# Main_bord.net
KiCad netlist of a schematic drawn in EAGLE
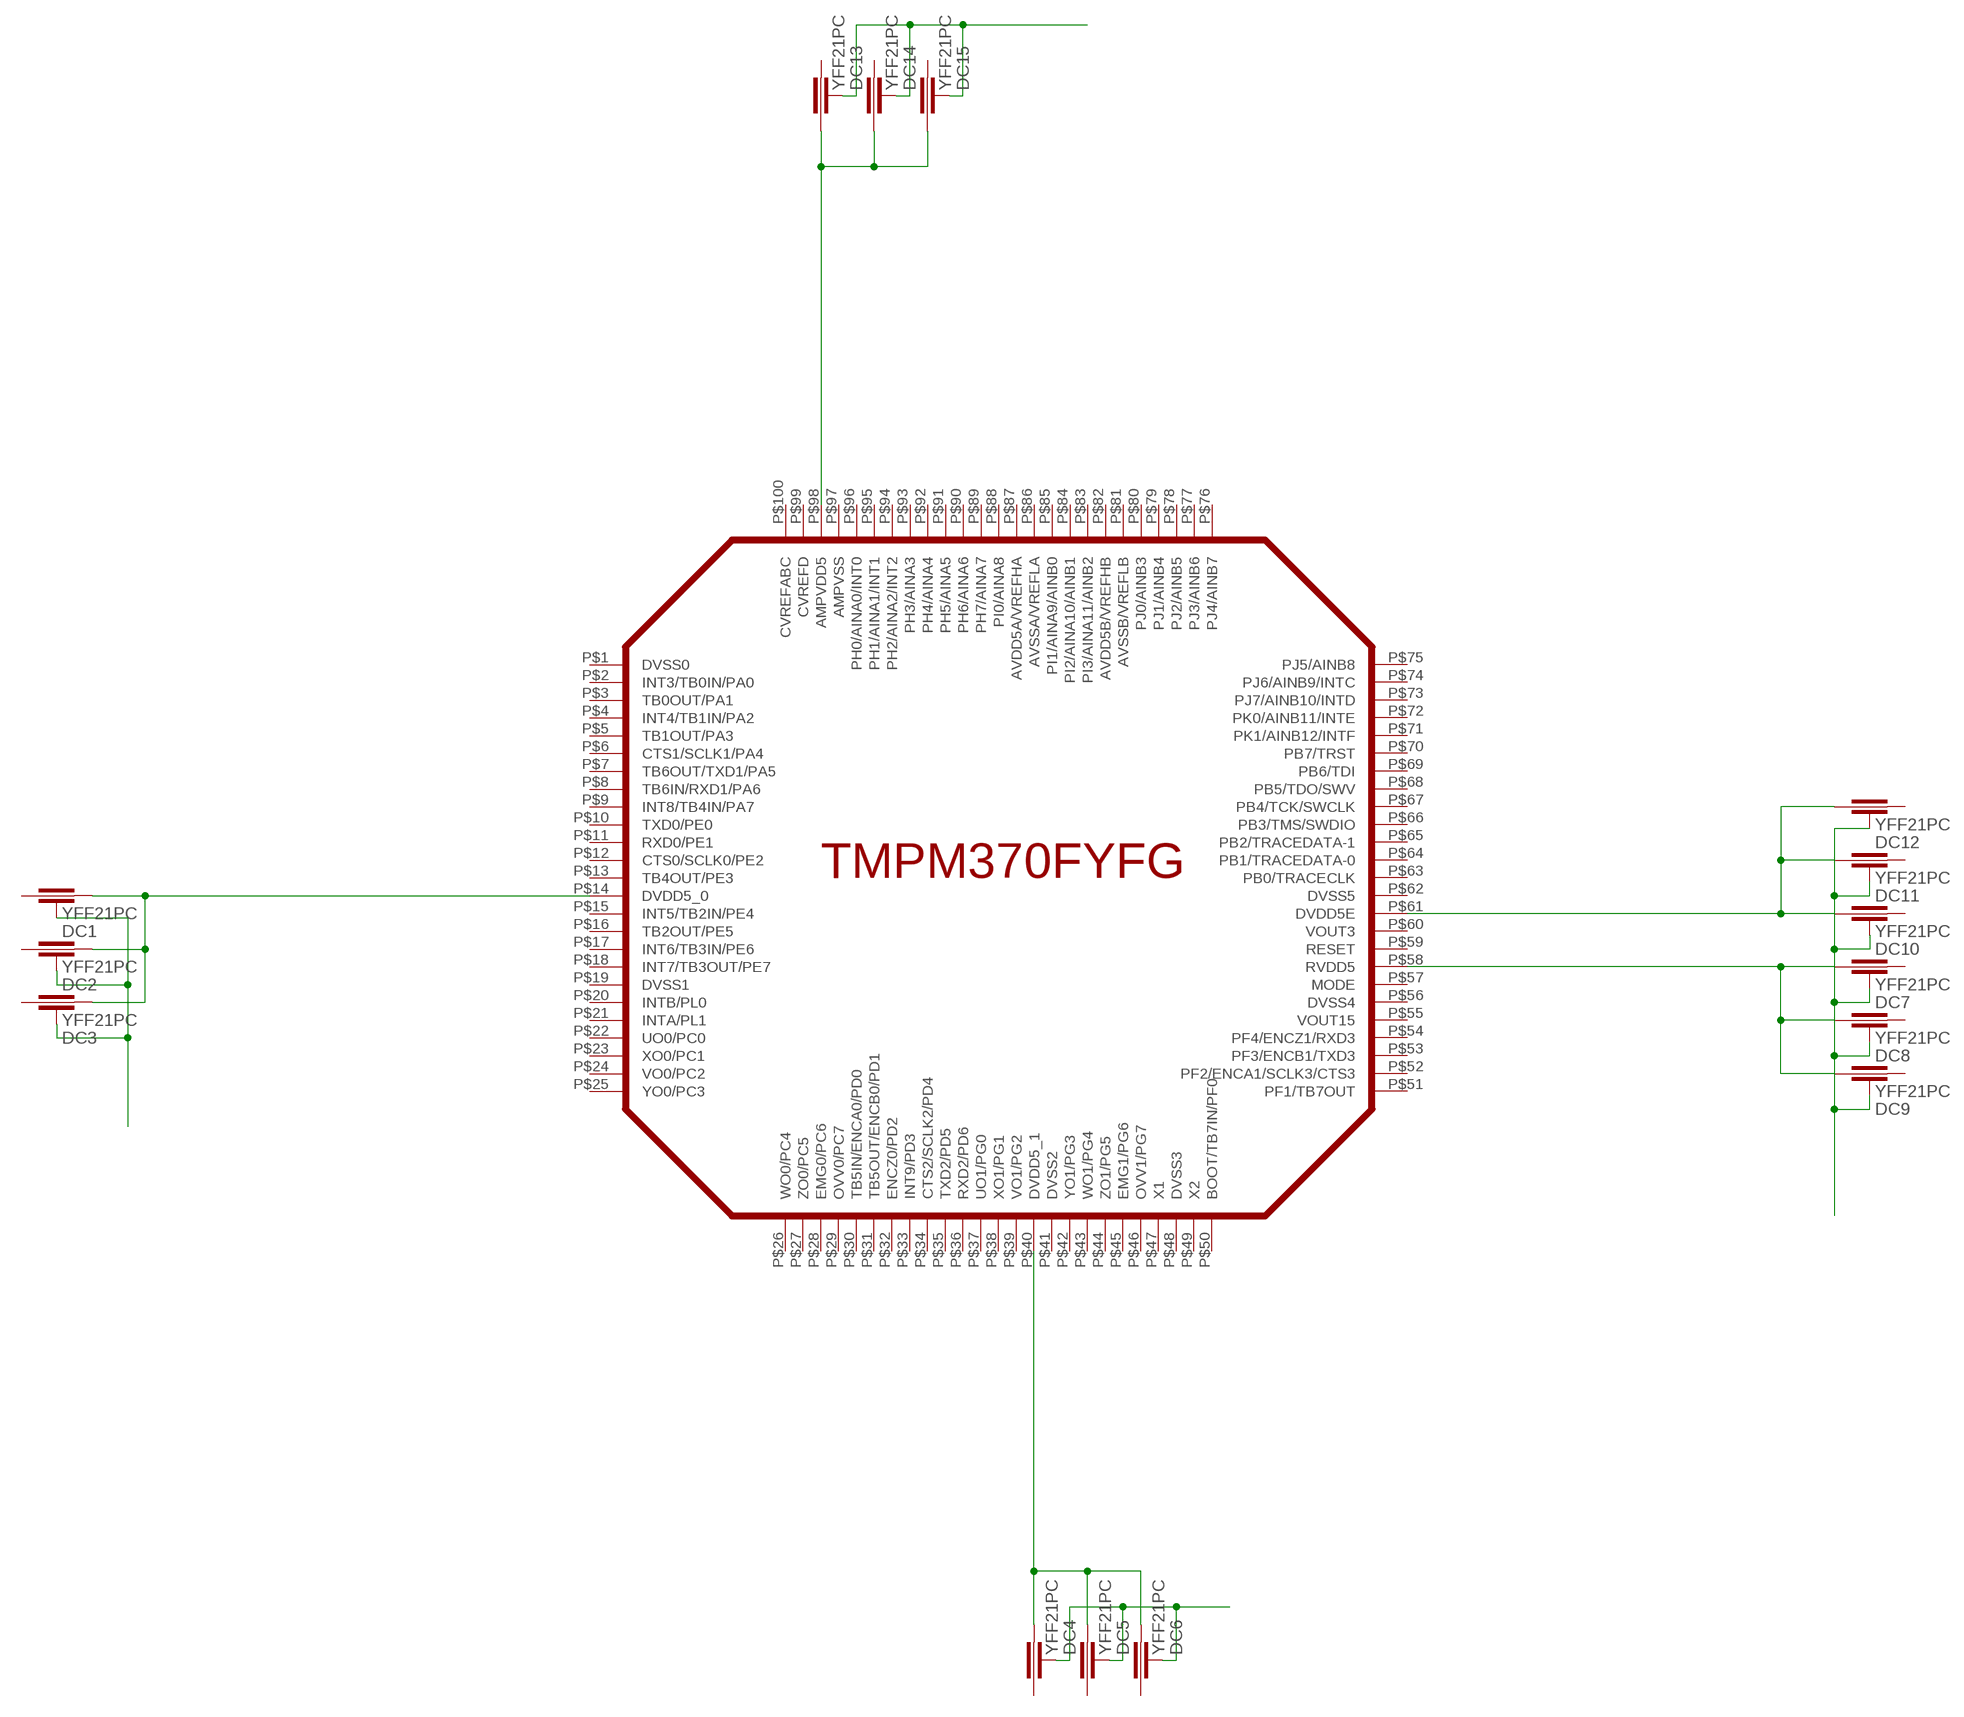
[diagram p0: schematic, sheet 1]

(export (version "E")
  (design (tool "Eeschema 10.0.6"))
  (components
    (comp (ref "DC1")
      (value "YFF21PC")
      (footprint "eagle-import:YFF21PC")
      (libsource (lib "eagle-import") (part "YFF21PC"))
    )
    (comp (ref "DC2")
      (value "YFF21PC")
      (footprint "eagle-import:YFF21PC")
      (libsource (lib "eagle-import") (part "YFF21PC"))
    )
    (comp (ref "DC3")
      (value "YFF21PC")
      (footprint "eagle-import:YFF21PC")
      (libsource (lib "eagle-import") (part "YFF21PC"))
    )
    (comp (ref "DC4")
      (value "YFF21PC")
      (footprint "eagle-import:YFF21PC")
      (libsource (lib "eagle-import") (part "YFF21PC"))
    )
    (comp (ref "DC5")
      (value "YFF21PC")
      (footprint "eagle-import:YFF21PC")
      (libsource (lib "eagle-import") (part "YFF21PC"))
    )
    (comp (ref "DC6")
      (value "YFF21PC")
      (footprint "eagle-import:YFF21PC")
      (libsource (lib "eagle-import") (part "YFF21PC"))
    )
    (comp (ref "DC7")
      (value "YFF21PC")
      (footprint "eagle-import:YFF21PC")
      (libsource (lib "eagle-import") (part "YFF21PC"))
    )
    (comp (ref "DC8")
      (value "YFF21PC")
      (footprint "eagle-import:YFF21PC")
      (libsource (lib "eagle-import") (part "YFF21PC"))
    )
    (comp (ref "DC9")
      (value "YFF21PC")
      (footprint "eagle-import:YFF21PC")
      (libsource (lib "eagle-import") (part "YFF21PC"))
    )
    (comp (ref "DC10")
      (value "YFF21PC")
      (footprint "eagle-import:YFF21PC")
      (libsource (lib "eagle-import") (part "YFF21PC"))
    )
    (comp (ref "DC11")
      (value "YFF21PC")
      (footprint "eagle-import:YFF21PC")
      (libsource (lib "eagle-import") (part "YFF21PC"))
    )
    (comp (ref "DC12")
      (value "YFF21PC")
      (footprint "eagle-import:YFF21PC")
      (libsource (lib "eagle-import") (part "YFF21PC"))
    )
    (comp (ref "DC13")
      (value "YFF21PC")
      (footprint "eagle-import:YFF21PC")
      (libsource (lib "eagle-import") (part "YFF21PC"))
    )
    (comp (ref "DC14")
      (value "YFF21PC")
      (footprint "eagle-import:YFF21PC")
      (libsource (lib "eagle-import") (part "YFF21PC"))
    )
    (comp (ref "DC15")
      (value "YFF21PC")
      (footprint "eagle-import:YFF21PC")
      (libsource (lib "eagle-import") (part "YFF21PC"))
    )
    (comp (ref "IC1")
      (value "TMPM370FYFG")
      (footprint "eagle-import:LQFP100-P-1414-0.50H")
      (libsource (lib "eagle-import") (part "TMPM370FYFG"))
    )
  )
  (nets
    (net (code "1") (name "Net-(DC1-GND-PadGND1)") (class "Default")
      (node (ref "DC1") (pin "GND1") (pinfunction "GND_GND1") (pintype "bidirectional"))
      (node (ref "DC1") (pin "GND2") (pinfunction "GND_GND2") (pintype "bidirectional"))
      (node (ref "DC2") (pin "GND1") (pinfunction "GND_GND1") (pintype "bidirectional"))
      (node (ref "DC2") (pin "GND2") (pinfunction "GND_GND2") (pintype "bidirectional"))
      (node (ref "DC3") (pin "GND1") (pinfunction "GND_GND1") (pintype "bidirectional"))
      (node (ref "DC3") (pin "GND2") (pinfunction "GND_GND2") (pintype "bidirectional"))
    )
    (net (code "2") (name "Net-(DC4-GND-PadGND1)") (class "Default")
      (node (ref "DC4") (pin "GND1") (pinfunction "GND_GND1") (pintype "bidirectional"))
      (node (ref "DC4") (pin "GND2") (pinfunction "GND_GND2") (pintype "bidirectional"))
      (node (ref "DC5") (pin "GND1") (pinfunction "GND_GND1") (pintype "bidirectional"))
      (node (ref "DC5") (pin "GND2") (pinfunction "GND_GND2") (pintype "bidirectional"))
      (node (ref "DC6") (pin "GND1") (pinfunction "GND_GND1") (pintype "bidirectional"))
      (node (ref "DC6") (pin "GND2") (pinfunction "GND_GND2") (pintype "bidirectional"))
    )
    (net (code "3") (name "Net-(DC10-GND-PadGND1)") (class "Default")
      (node (ref "DC10") (pin "GND1") (pinfunction "GND_GND1") (pintype "bidirectional"))
      (node (ref "DC10") (pin "GND2") (pinfunction "GND_GND2") (pintype "bidirectional"))
      (node (ref "DC11") (pin "GND1") (pinfunction "GND_GND1") (pintype "bidirectional"))
      (node (ref "DC11") (pin "GND2") (pinfunction "GND_GND2") (pintype "bidirectional"))
      (node (ref "DC12") (pin "GND1") (pinfunction "GND_GND1") (pintype "bidirectional"))
      (node (ref "DC12") (pin "GND2") (pinfunction "GND_GND2") (pintype "bidirectional"))
      (node (ref "DC7") (pin "GND1") (pinfunction "GND_GND1") (pintype "bidirectional"))
      (node (ref "DC7") (pin "GND2") (pinfunction "GND_GND2") (pintype "bidirectional"))
      (node (ref "DC8") (pin "GND1") (pinfunction "GND_GND1") (pintype "bidirectional"))
      (node (ref "DC8") (pin "GND2") (pinfunction "GND_GND2") (pintype "bidirectional"))
      (node (ref "DC9") (pin "GND1") (pinfunction "GND_GND1") (pintype "bidirectional"))
      (node (ref "DC9") (pin "GND2") (pinfunction "GND_GND2") (pintype "bidirectional"))
    )
    (net (code "4") (name "Net-(DC13-GND-PadGND1)") (class "Default")
      (node (ref "DC13") (pin "GND1") (pinfunction "GND_GND1") (pintype "bidirectional"))
      (node (ref "DC13") (pin "GND2") (pinfunction "GND_GND2") (pintype "bidirectional"))
      (node (ref "DC14") (pin "GND1") (pinfunction "GND_GND1") (pintype "bidirectional"))
      (node (ref "DC14") (pin "GND2") (pinfunction "GND_GND2") (pintype "bidirectional"))
      (node (ref "DC15") (pin "GND1") (pinfunction "GND_GND1") (pintype "bidirectional"))
      (node (ref "DC15") (pin "GND2") (pinfunction "GND_GND2") (pintype "bidirectional"))
    )
    (net (code "5") (name "Net-(IC1-AMPVDD5)") (class "Default")
      (node (ref "DC13") (pin "P$1") (pinfunction "P$1_P$1") (pintype "bidirectional"))
      (node (ref "DC14") (pin "P$1") (pinfunction "P$1_P$1") (pintype "bidirectional"))
      (node (ref "DC15") (pin "P$1") (pinfunction "P$1_P$1") (pintype "bidirectional"))
      (node (ref "IC1") (pin "P$98") (pinfunction "AMPVDD5_P$98") (pintype "bidirectional"))
    )
    (net (code "6") (name "Net-(IC1-DVDD5E)") (class "Default")
      (node (ref "DC10") (pin "P$1") (pinfunction "P$1_P$1") (pintype "bidirectional"))
      (node (ref "DC11") (pin "P$1") (pinfunction "P$1_P$1") (pintype "bidirectional"))
      (node (ref "DC12") (pin "P$1") (pinfunction "P$1_P$1") (pintype "bidirectional"))
      (node (ref "IC1") (pin "P$61") (pinfunction "DVDD5E_P$61") (pintype "bidirectional"))
    )
    (net (code "7") (name "Net-(IC1-DVDD5_0)") (class "Default")
      (node (ref "DC1") (pin "P$2") (pinfunction "P$2_P$2") (pintype "bidirectional"))
      (node (ref "DC2") (pin "P$2") (pinfunction "P$2_P$2") (pintype "bidirectional"))
      (node (ref "DC3") (pin "P$2") (pinfunction "P$2_P$2") (pintype "bidirectional"))
      (node (ref "IC1") (pin "P$14") (pinfunction "DVDD5_0_P$14") (pintype "bidirectional"))
    )
    (net (code "8") (name "Net-(IC1-DVDD5_1)") (class "Default")
      (node (ref "DC4") (pin "P$2") (pinfunction "P$2_P$2") (pintype "bidirectional"))
      (node (ref "DC5") (pin "P$2") (pinfunction "P$2_P$2") (pintype "bidirectional"))
      (node (ref "DC6") (pin "P$2") (pinfunction "P$2_P$2") (pintype "bidirectional"))
      (node (ref "IC1") (pin "P$40") (pinfunction "DVDD5_1_P$40") (pintype "bidirectional"))
    )
    (net (code "9") (name "Net-(IC1-RVDD5)") (class "Default")
      (node (ref "DC7") (pin "P$1") (pinfunction "P$1_P$1") (pintype "bidirectional"))
      (node (ref "DC8") (pin "P$1") (pinfunction "P$1_P$1") (pintype "bidirectional"))
      (node (ref "DC9") (pin "P$1") (pinfunction "P$1_P$1") (pintype "bidirectional"))
      (node (ref "IC1") (pin "P$58") (pinfunction "RVDD5_P$58") (pintype "bidirectional"))
    )
    (net (code "10") (name "unconnected-(DC1-PadP$1)") (class "Default")
      (node (ref "DC1") (pin "P$1") (pinfunction "P$1_P$1") (pintype "bidirectional"))
    )
    (net (code "11") (name "unconnected-(DC2-PadP$1)") (class "Default")
      (node (ref "DC2") (pin "P$1") (pinfunction "P$1_P$1") (pintype "bidirectional"))
    )
    (net (code "12") (name "unconnected-(DC3-PadP$1)") (class "Default")
      (node (ref "DC3") (pin "P$1") (pinfunction "P$1_P$1") (pintype "bidirectional"))
    )
    (net (code "13") (name "unconnected-(DC4-PadP$1)") (class "Default")
      (node (ref "DC4") (pin "P$1") (pinfunction "P$1_P$1") (pintype "bidirectional"))
    )
    (net (code "14") (name "unconnected-(DC5-PadP$1)") (class "Default")
      (node (ref "DC5") (pin "P$1") (pinfunction "P$1_P$1") (pintype "bidirectional"))
    )
    (net (code "15") (name "unconnected-(DC6-PadP$1)") (class "Default")
      (node (ref "DC6") (pin "P$1") (pinfunction "P$1_P$1") (pintype "bidirectional"))
    )
    (net (code "16") (name "unconnected-(DC7-PadP$2)") (class "Default")
      (node (ref "DC7") (pin "P$2") (pinfunction "P$2_P$2") (pintype "bidirectional"))
    )
    (net (code "17") (name "unconnected-(DC8-PadP$2)") (class "Default")
      (node (ref "DC8") (pin "P$2") (pinfunction "P$2_P$2") (pintype "bidirectional"))
    )
    (net (code "18") (name "unconnected-(DC9-PadP$2)") (class "Default")
      (node (ref "DC9") (pin "P$2") (pinfunction "P$2_P$2") (pintype "bidirectional"))
    )
    (net (code "19") (name "unconnected-(DC10-PadP$2)") (class "Default")
      (node (ref "DC10") (pin "P$2") (pinfunction "P$2_P$2") (pintype "bidirectional"))
    )
    (net (code "20") (name "unconnected-(DC11-PadP$2)") (class "Default")
      (node (ref "DC11") (pin "P$2") (pinfunction "P$2_P$2") (pintype "bidirectional"))
    )
    (net (code "21") (name "unconnected-(DC12-PadP$2)") (class "Default")
      (node (ref "DC12") (pin "P$2") (pinfunction "P$2_P$2") (pintype "bidirectional"))
    )
    (net (code "22") (name "unconnected-(DC13-PadP$2)") (class "Default")
      (node (ref "DC13") (pin "P$2") (pinfunction "P$2_P$2") (pintype "bidirectional"))
    )
    (net (code "23") (name "unconnected-(DC14-PadP$2)") (class "Default")
      (node (ref "DC14") (pin "P$2") (pinfunction "P$2_P$2") (pintype "bidirectional"))
    )
    (net (code "24") (name "unconnected-(DC15-PadP$2)") (class "Default")
      (node (ref "DC15") (pin "P$2") (pinfunction "P$2_P$2") (pintype "bidirectional"))
    )
    (net (code "25") (name "unconnected-(IC1-AMPVSS-PadP$97)") (class "Default")
      (node (ref "IC1") (pin "P$97") (pinfunction "AMPVSS_P$97") (pintype "bidirectional"))
    )
    (net (code "26") (name "unconnected-(IC1-AVDD5A{slash}VREFHA-PadP$87)") (class "Default")
      (node (ref "IC1") (pin "P$87") (pinfunction "AVDD5A/VREFHA_P$87") (pintype "bidirectional"))
    )
    (net (code "27") (name "unconnected-(IC1-AVDD5B{slash}VREFHB-PadP$82)") (class "Default")
      (node (ref "IC1") (pin "P$82") (pinfunction "AVDD5B/VREFHB_P$82") (pintype "bidirectional"))
    )
    (net (code "28") (name "unconnected-(IC1-AVSSA{slash}VREFLA-PadP$86)") (class "Default")
      (node (ref "IC1") (pin "P$86") (pinfunction "AVSSA/VREFLA_P$86") (pintype "bidirectional"))
    )
    (net (code "29") (name "unconnected-(IC1-AVSSB{slash}VREFLB-PadP$81)") (class "Default")
      (node (ref "IC1") (pin "P$81") (pinfunction "AVSSB/VREFLB_P$81") (pintype "bidirectional"))
    )
    (net (code "30") (name "unconnected-(IC1-BOOT{slash}TB7IN{slash}PF0-PadP$50)") (class "Default")
      (node (ref "IC1") (pin "P$50") (pinfunction "BOOT/TB7IN/PF0_P$50") (pintype "bidirectional"))
    )
    (net (code "31") (name "unconnected-(IC1-CTS0{slash}SCLK0{slash}PE2-PadP$12)") (class "Default")
      (node (ref "IC1") (pin "P$12") (pinfunction "CTS0/SCLK0/PE2_P$12") (pintype "bidirectional"))
    )
    (net (code "32") (name "unconnected-(IC1-CTS1{slash}SCLK1{slash}PA4-PadP$6)") (class "Default")
      (node (ref "IC1") (pin "P$6") (pinfunction "CTS1/SCLK1/PA4_P$6") (pintype "bidirectional"))
    )
    (net (code "33") (name "unconnected-(IC1-CTS2{slash}SCLK2{slash}PD4-PadP$34)") (class "Default")
      (node (ref "IC1") (pin "P$34") (pinfunction "CTS2/SCLK2/PD4_P$34") (pintype "bidirectional"))
    )
    (net (code "34") (name "unconnected-(IC1-CVREFABC-PadP$100)") (class "Default")
      (node (ref "IC1") (pin "P$100") (pinfunction "CVREFABC_P$100") (pintype "bidirectional"))
    )
    (net (code "35") (name "unconnected-(IC1-CVREFD-PadP$99)") (class "Default")
      (node (ref "IC1") (pin "P$99") (pinfunction "CVREFD_P$99") (pintype "bidirectional"))
    )
    (net (code "36") (name "unconnected-(IC1-DVSS0-PadP$1)") (class "Default")
      (node (ref "IC1") (pin "P$1") (pinfunction "DVSS0_P$1") (pintype "bidirectional"))
    )
    (net (code "37") (name "unconnected-(IC1-DVSS1-PadP$19)") (class "Default")
      (node (ref "IC1") (pin "P$19") (pinfunction "DVSS1_P$19") (pintype "bidirectional"))
    )
    (net (code "38") (name "unconnected-(IC1-DVSS2-PadP$41)") (class "Default")
      (node (ref "IC1") (pin "P$41") (pinfunction "DVSS2_P$41") (pintype "bidirectional"))
    )
    (net (code "39") (name "unconnected-(IC1-DVSS3-PadP$48)") (class "Default")
      (node (ref "IC1") (pin "P$48") (pinfunction "DVSS3_P$48") (pintype "bidirectional"))
    )
    (net (code "40") (name "unconnected-(IC1-DVSS4-PadP$56)") (class "Default")
      (node (ref "IC1") (pin "P$56") (pinfunction "DVSS4_P$56") (pintype "bidirectional"))
    )
    (net (code "41") (name "unconnected-(IC1-DVSS5-PadP$62)") (class "Default")
      (node (ref "IC1") (pin "P$62") (pinfunction "DVSS5_P$62") (pintype "bidirectional"))
    )
    (net (code "42") (name "unconnected-(IC1-EMG0{slash}PC6-PadP$28)") (class "Default")
      (node (ref "IC1") (pin "P$28") (pinfunction "EMG0/PC6_P$28") (pintype "bidirectional"))
    )
    (net (code "43") (name "unconnected-(IC1-EMG1{slash}PG6-PadP$45)") (class "Default")
      (node (ref "IC1") (pin "P$45") (pinfunction "EMG1/PG6_P$45") (pintype "bidirectional"))
    )
    (net (code "44") (name "unconnected-(IC1-ENCZ0{slash}PD2-PadP$32)") (class "Default")
      (node (ref "IC1") (pin "P$32") (pinfunction "ENCZ0/PD2_P$32") (pintype "bidirectional"))
    )
    (net (code "45") (name "unconnected-(IC1-INT3{slash}TB0IN{slash}PA0-PadP$2)") (class "Default")
      (node (ref "IC1") (pin "P$2") (pinfunction "INT3/TB0IN/PA0_P$2") (pintype "bidirectional"))
    )
    (net (code "46") (name "unconnected-(IC1-INT4{slash}TB1IN{slash}PA2-PadP$4)") (class "Default")
      (node (ref "IC1") (pin "P$4") (pinfunction "INT4/TB1IN/PA2_P$4") (pintype "bidirectional"))
    )
    (net (code "47") (name "unconnected-(IC1-INT5{slash}TB2IN{slash}PE4-PadP$15)") (class "Default")
      (node (ref "IC1") (pin "P$15") (pinfunction "INT5/TB2IN/PE4_P$15") (pintype "bidirectional"))
    )
    (net (code "48") (name "unconnected-(IC1-INT6{slash}TB3IN{slash}PE6-PadP$17)") (class "Default")
      (node (ref "IC1") (pin "P$17") (pinfunction "INT6/TB3IN/PE6_P$17") (pintype "bidirectional"))
    )
    (net (code "49") (name "unconnected-(IC1-INT7{slash}TB3OUT{slash}PE7-PadP$18)") (class "Default")
      (node (ref "IC1") (pin "P$18") (pinfunction "INT7/TB3OUT/PE7_P$18") (pintype "bidirectional"))
    )
    (net (code "50") (name "unconnected-(IC1-INT8{slash}TB4IN{slash}PA7-PadP$9)") (class "Default")
      (node (ref "IC1") (pin "P$9") (pinfunction "INT8/TB4IN/PA7_P$9") (pintype "bidirectional"))
    )
    (net (code "51") (name "unconnected-(IC1-INT9{slash}PD3-PadP$33)") (class "Default")
      (node (ref "IC1") (pin "P$33") (pinfunction "INT9/PD3_P$33") (pintype "bidirectional"))
    )
    (net (code "52") (name "unconnected-(IC1-INTA{slash}PL1-PadP$21)") (class "Default")
      (node (ref "IC1") (pin "P$21") (pinfunction "INTA/PL1_P$21") (pintype "bidirectional"))
    )
    (net (code "53") (name "unconnected-(IC1-INTB{slash}PL0-PadP$20)") (class "Default")
      (node (ref "IC1") (pin "P$20") (pinfunction "INTB/PL0_P$20") (pintype "bidirectional"))
    )
    (net (code "54") (name "unconnected-(IC1-MODE-PadP$57)") (class "Default")
      (node (ref "IC1") (pin "P$57") (pinfunction "MODE_P$57") (pintype "bidirectional"))
    )
    (net (code "55") (name "unconnected-(IC1-OVV0{slash}PC7-PadP$29)") (class "Default")
      (node (ref "IC1") (pin "P$29") (pinfunction "OVV0/PC7_P$29") (pintype "bidirectional"))
    )
    (net (code "56") (name "unconnected-(IC1-OVV1{slash}PG7-PadP$46)") (class "Default")
      (node (ref "IC1") (pin "P$46") (pinfunction "OVV1/PG7_P$46") (pintype "bidirectional"))
    )
    (net (code "57") (name "unconnected-(IC1-PB0{slash}TRACECLK-PadP$63)") (class "Default")
      (node (ref "IC1") (pin "P$63") (pinfunction "PB0/TRACECLK_P$63") (pintype "bidirectional"))
    )
    (net (code "58") (name "unconnected-(IC1-PB1{slash}TRACEDATA-0-PadP$64)") (class "Default")
      (node (ref "IC1") (pin "P$64") (pinfunction "PB1/TRACEDATA-0_P$64") (pintype "bidirectional"))
    )
    (net (code "59") (name "unconnected-(IC1-PB2{slash}TRACEDATA-1-PadP$65)") (class "Default")
      (node (ref "IC1") (pin "P$65") (pinfunction "PB2/TRACEDATA-1_P$65") (pintype "bidirectional"))
    )
    (net (code "60") (name "unconnected-(IC1-PB3{slash}TMS{slash}SWDIO-PadP$66)") (class "Default")
      (node (ref "IC1") (pin "P$66") (pinfunction "PB3/TMS/SWDIO_P$66") (pintype "bidirectional"))
    )
    (net (code "61") (name "unconnected-(IC1-PB4{slash}TCK{slash}SWCLK-PadP$67)") (class "Default")
      (node (ref "IC1") (pin "P$67") (pinfunction "PB4/TCK/SWCLK_P$67") (pintype "bidirectional"))
    )
    (net (code "62") (name "unconnected-(IC1-PB5{slash}TDO{slash}SWV-PadP$68)") (class "Default")
      (node (ref "IC1") (pin "P$68") (pinfunction "PB5/TDO/SWV_P$68") (pintype "bidirectional"))
    )
    (net (code "63") (name "unconnected-(IC1-PB6{slash}TDI-PadP$69)") (class "Default")
      (node (ref "IC1") (pin "P$69") (pinfunction "PB6/TDI_P$69") (pintype "bidirectional"))
    )
    (net (code "64") (name "unconnected-(IC1-PB7{slash}TRST-PadP$70)") (class "Default")
      (node (ref "IC1") (pin "P$70") (pinfunction "PB7/TRST_P$70") (pintype "bidirectional"))
    )
    (net (code "65") (name "unconnected-(IC1-PF1{slash}TB7OUT-PadP$51)") (class "Default")
      (node (ref "IC1") (pin "P$51") (pinfunction "PF1/TB7OUT_P$51") (pintype "bidirectional"))
    )
    (net (code "66") (name "unconnected-(IC1-PF2{slash}ENCA1{slash}SCLK3{slash}CTS3-PadP$52)") (class "Default")
      (node (ref "IC1") (pin "P$52") (pinfunction "PF2/ENCA1/SCLK3/CTS3_P$52") (pintype "bidirectional"))
    )
    (net (code "67") (name "unconnected-(IC1-PF3{slash}ENCB1{slash}TXD3-PadP$53)") (class "Default")
      (node (ref "IC1") (pin "P$53") (pinfunction "PF3/ENCB1/TXD3_P$53") (pintype "bidirectional"))
    )
    (net (code "68") (name "unconnected-(IC1-PF4{slash}ENCZ1{slash}RXD3-PadP$54)") (class "Default")
      (node (ref "IC1") (pin "P$54") (pinfunction "PF4/ENCZ1/RXD3_P$54") (pintype "bidirectional"))
    )
    (net (code "69") (name "unconnected-(IC1-PH0{slash}AINA0{slash}INT0-PadP$96)") (class "Default")
      (node (ref "IC1") (pin "P$96") (pinfunction "PH0/AINA0/INT0_P$96") (pintype "bidirectional"))
    )
    (net (code "70") (name "unconnected-(IC1-PH1{slash}AINA1{slash}INT1-PadP$95)") (class "Default")
      (node (ref "IC1") (pin "P$95") (pinfunction "PH1/AINA1/INT1_P$95") (pintype "bidirectional"))
    )
    (net (code "71") (name "unconnected-(IC1-PH2{slash}AINA2{slash}INT2-PadP$94)") (class "Default")
      (node (ref "IC1") (pin "P$94") (pinfunction "PH2/AINA2/INT2_P$94") (pintype "bidirectional"))
    )
    (net (code "72") (name "unconnected-(IC1-PH3{slash}AINA3-PadP$93)") (class "Default")
      (node (ref "IC1") (pin "P$93") (pinfunction "PH3/AINA3_P$93") (pintype "bidirectional"))
    )
    (net (code "73") (name "unconnected-(IC1-PH4{slash}AINA4-PadP$92)") (class "Default")
      (node (ref "IC1") (pin "P$92") (pinfunction "PH4/AINA4_P$92") (pintype "bidirectional"))
    )
    (net (code "74") (name "unconnected-(IC1-PH5{slash}AINA5-PadP$91)") (class "Default")
      (node (ref "IC1") (pin "P$91") (pinfunction "PH5/AINA5_P$91") (pintype "bidirectional"))
    )
    (net (code "75") (name "unconnected-(IC1-PH6{slash}AINA6-PadP$90)") (class "Default")
      (node (ref "IC1") (pin "P$90") (pinfunction "PH6/AINA6_P$90") (pintype "bidirectional"))
    )
    (net (code "76") (name "unconnected-(IC1-PH7{slash}AINA7-PadP$89)") (class "Default")
      (node (ref "IC1") (pin "P$89") (pinfunction "PH7/AINA7_P$89") (pintype "bidirectional"))
    )
    (net (code "77") (name "unconnected-(IC1-PI0{slash}AINA8-PadP$88)") (class "Default")
      (node (ref "IC1") (pin "P$88") (pinfunction "PI0/AINA8_P$88") (pintype "bidirectional"))
    )
    (net (code "78") (name "unconnected-(IC1-PI1{slash}AINA9{slash}AINB0-PadP$85)") (class "Default")
      (node (ref "IC1") (pin "P$85") (pinfunction "PI1/AINA9/AINB0_P$85") (pintype "bidirectional"))
    )
    (net (code "79") (name "unconnected-(IC1-PI2{slash}AINA10{slash}AINB1-PadP$84)") (class "Default")
      (node (ref "IC1") (pin "P$84") (pinfunction "PI2/AINA10/AINB1_P$84") (pintype "bidirectional"))
    )
    (net (code "80") (name "unconnected-(IC1-PI3{slash}AINA11{slash}AINB2-PadP$83)") (class "Default")
      (node (ref "IC1") (pin "P$83") (pinfunction "PI3/AINA11/AINB2_P$83") (pintype "bidirectional"))
    )
    (net (code "81") (name "unconnected-(IC1-PJ0{slash}AINB3-PadP$80)") (class "Default")
      (node (ref "IC1") (pin "P$80") (pinfunction "PJ0/AINB3_P$80") (pintype "bidirectional"))
    )
    (net (code "82") (name "unconnected-(IC1-PJ1{slash}AINB4-PadP$79)") (class "Default")
      (node (ref "IC1") (pin "P$79") (pinfunction "PJ1/AINB4_P$79") (pintype "bidirectional"))
    )
    (net (code "83") (name "unconnected-(IC1-PJ2{slash}AINB5-PadP$78)") (class "Default")
      (node (ref "IC1") (pin "P$78") (pinfunction "PJ2/AINB5_P$78") (pintype "bidirectional"))
    )
    (net (code "84") (name "unconnected-(IC1-PJ3{slash}AINB6-PadP$77)") (class "Default")
      (node (ref "IC1") (pin "P$77") (pinfunction "PJ3/AINB6_P$77") (pintype "bidirectional"))
    )
    (net (code "85") (name "unconnected-(IC1-PJ4{slash}AINB7-PadP$76)") (class "Default")
      (node (ref "IC1") (pin "P$76") (pinfunction "PJ4/AINB7_P$76") (pintype "bidirectional"))
    )
    (net (code "86") (name "unconnected-(IC1-PJ5{slash}AINB8-PadP$75)") (class "Default")
      (node (ref "IC1") (pin "P$75") (pinfunction "PJ5/AINB8_P$75") (pintype "bidirectional"))
    )
    (net (code "87") (name "unconnected-(IC1-PJ6{slash}AINB9{slash}INTC-PadP$74)") (class "Default")
      (node (ref "IC1") (pin "P$74") (pinfunction "PJ6/AINB9/INTC_P$74") (pintype "bidirectional"))
    )
    (net (code "88") (name "unconnected-(IC1-PJ7{slash}AINB10{slash}INTD-PadP$73)") (class "Default")
      (node (ref "IC1") (pin "P$73") (pinfunction "PJ7/AINB10/INTD_P$73") (pintype "bidirectional"))
    )
    (net (code "89") (name "unconnected-(IC1-PK0{slash}AINB11{slash}INTE-PadP$72)") (class "Default")
      (node (ref "IC1") (pin "P$72") (pinfunction "PK0/AINB11/INTE_P$72") (pintype "bidirectional"))
    )
    (net (code "90") (name "unconnected-(IC1-PK1{slash}AINB12{slash}INTF-PadP$71)") (class "Default")
      (node (ref "IC1") (pin "P$71") (pinfunction "PK1/AINB12/INTF_P$71") (pintype "bidirectional"))
    )
    (net (code "91") (name "unconnected-(IC1-RESET-PadP$59)") (class "Default")
      (node (ref "IC1") (pin "P$59") (pinfunction "RESET_P$59") (pintype "bidirectional"))
    )
    (net (code "92") (name "unconnected-(IC1-RXD0{slash}PE1-PadP$11)") (class "Default")
      (node (ref "IC1") (pin "P$11") (pinfunction "RXD0/PE1_P$11") (pintype "bidirectional"))
    )
    (net (code "93") (name "unconnected-(IC1-RXD2{slash}PD6-PadP$36)") (class "Default")
      (node (ref "IC1") (pin "P$36") (pinfunction "RXD2/PD6_P$36") (pintype "bidirectional"))
    )
    (net (code "94") (name "unconnected-(IC1-TB0OUT{slash}PA1-PadP$3)") (class "Default")
      (node (ref "IC1") (pin "P$3") (pinfunction "TB0OUT/PA1_P$3") (pintype "bidirectional"))
    )
    (net (code "95") (name "unconnected-(IC1-TB1OUT{slash}PA3-PadP$5)") (class "Default")
      (node (ref "IC1") (pin "P$5") (pinfunction "TB1OUT/PA3_P$5") (pintype "bidirectional"))
    )
    (net (code "96") (name "unconnected-(IC1-TB2OUT{slash}PE5-PadP$16)") (class "Default")
      (node (ref "IC1") (pin "P$16") (pinfunction "TB2OUT/PE5_P$16") (pintype "bidirectional"))
    )
    (net (code "97") (name "unconnected-(IC1-TB4OUT{slash}PE3-PadP$13)") (class "Default")
      (node (ref "IC1") (pin "P$13") (pinfunction "TB4OUT/PE3_P$13") (pintype "bidirectional"))
    )
    (net (code "98") (name "unconnected-(IC1-TB5IN{slash}ENCA0{slash}PD0-PadP$30)") (class "Default")
      (node (ref "IC1") (pin "P$30") (pinfunction "TB5IN/ENCA0/PD0_P$30") (pintype "bidirectional"))
    )
    (net (code "99") (name "unconnected-(IC1-TB5OUT{slash}ENCB0{slash}PD1-PadP$31)") (class "Default")
      (node (ref "IC1") (pin "P$31") (pinfunction "TB5OUT/ENCB0/PD1_P$31") (pintype "bidirectional"))
    )
    (net (code "100") (name "unconnected-(IC1-TB6IN{slash}RXD1{slash}PA6-PadP$8)") (class "Default")
      (node (ref "IC1") (pin "P$8") (pinfunction "TB6IN/RXD1/PA6_P$8") (pintype "bidirectional"))
    )
    (net (code "101") (name "unconnected-(IC1-TB6OUT{slash}TXD1{slash}PA5-PadP$7)") (class "Default")
      (node (ref "IC1") (pin "P$7") (pinfunction "TB6OUT/TXD1/PA5_P$7") (pintype "bidirectional"))
    )
    (net (code "102") (name "unconnected-(IC1-TXD0{slash}PE0-PadP$10)") (class "Default")
      (node (ref "IC1") (pin "P$10") (pinfunction "TXD0/PE0_P$10") (pintype "bidirectional"))
    )
    (net (code "103") (name "unconnected-(IC1-TXD2{slash}PD5-PadP$35)") (class "Default")
      (node (ref "IC1") (pin "P$35") (pinfunction "TXD2/PD5_P$35") (pintype "bidirectional"))
    )
    (net (code "104") (name "unconnected-(IC1-UO0{slash}PC0-PadP$22)") (class "Default")
      (node (ref "IC1") (pin "P$22") (pinfunction "UO0/PC0_P$22") (pintype "bidirectional"))
    )
    (net (code "105") (name "unconnected-(IC1-UO1{slash}PG0-PadP$37)") (class "Default")
      (node (ref "IC1") (pin "P$37") (pinfunction "UO1/PG0_P$37") (pintype "bidirectional"))
    )
    (net (code "106") (name "unconnected-(IC1-VO0{slash}PC2-PadP$24)") (class "Default")
      (node (ref "IC1") (pin "P$24") (pinfunction "VO0/PC2_P$24") (pintype "bidirectional"))
    )
    (net (code "107") (name "unconnected-(IC1-VO1{slash}PG2-PadP$39)") (class "Default")
      (node (ref "IC1") (pin "P$39") (pinfunction "VO1/PG2_P$39") (pintype "bidirectional"))
    )
    (net (code "108") (name "unconnected-(IC1-VOUT3-PadP$60)") (class "Default")
      (node (ref "IC1") (pin "P$60") (pinfunction "VOUT3_P$60") (pintype "bidirectional"))
    )
    (net (code "109") (name "unconnected-(IC1-VOUT15-PadP$55)") (class "Default")
      (node (ref "IC1") (pin "P$55") (pinfunction "VOUT15_P$55") (pintype "bidirectional"))
    )
    (net (code "110") (name "unconnected-(IC1-WO0{slash}PC4-PadP$26)") (class "Default")
      (node (ref "IC1") (pin "P$26") (pinfunction "WO0/PC4_P$26") (pintype "bidirectional"))
    )
    (net (code "111") (name "unconnected-(IC1-WO1{slash}PG4-PadP$43)") (class "Default")
      (node (ref "IC1") (pin "P$43") (pinfunction "WO1/PG4_P$43") (pintype "bidirectional"))
    )
    (net (code "112") (name "unconnected-(IC1-X1-PadP$47)") (class "Default")
      (node (ref "IC1") (pin "P$47") (pinfunction "X1_P$47") (pintype "bidirectional"))
    )
    (net (code "113") (name "unconnected-(IC1-X2-PadP$49)") (class "Default")
      (node (ref "IC1") (pin "P$49") (pinfunction "X2_P$49") (pintype "bidirectional"))
    )
    (net (code "114") (name "unconnected-(IC1-XO0{slash}PC1-PadP$23)") (class "Default")
      (node (ref "IC1") (pin "P$23") (pinfunction "XO0/PC1_P$23") (pintype "bidirectional"))
    )
    (net (code "115") (name "unconnected-(IC1-XO1{slash}PG1-PadP$38)") (class "Default")
      (node (ref "IC1") (pin "P$38") (pinfunction "XO1/PG1_P$38") (pintype "bidirectional"))
    )
    (net (code "116") (name "unconnected-(IC1-YO0{slash}PC3-PadP$25)") (class "Default")
      (node (ref "IC1") (pin "P$25") (pinfunction "YO0/PC3_P$25") (pintype "bidirectional"))
    )
    (net (code "117") (name "unconnected-(IC1-YO1{slash}PG3-PadP$42)") (class "Default")
      (node (ref "IC1") (pin "P$42") (pinfunction "YO1/PG3_P$42") (pintype "bidirectional"))
    )
    (net (code "118") (name "unconnected-(IC1-ZO0{slash}PC5-PadP$27)") (class "Default")
      (node (ref "IC1") (pin "P$27") (pinfunction "ZO0/PC5_P$27") (pintype "bidirectional"))
    )
    (net (code "119") (name "unconnected-(IC1-ZO1{slash}PG5-PadP$44)") (class "Default")
      (node (ref "IC1") (pin "P$44") (pinfunction "ZO1/PG5_P$44") (pintype "bidirectional"))
    )
  )
)
